# sensor-header.net
KiCad netlist of a schematic drawn in Altium Designer
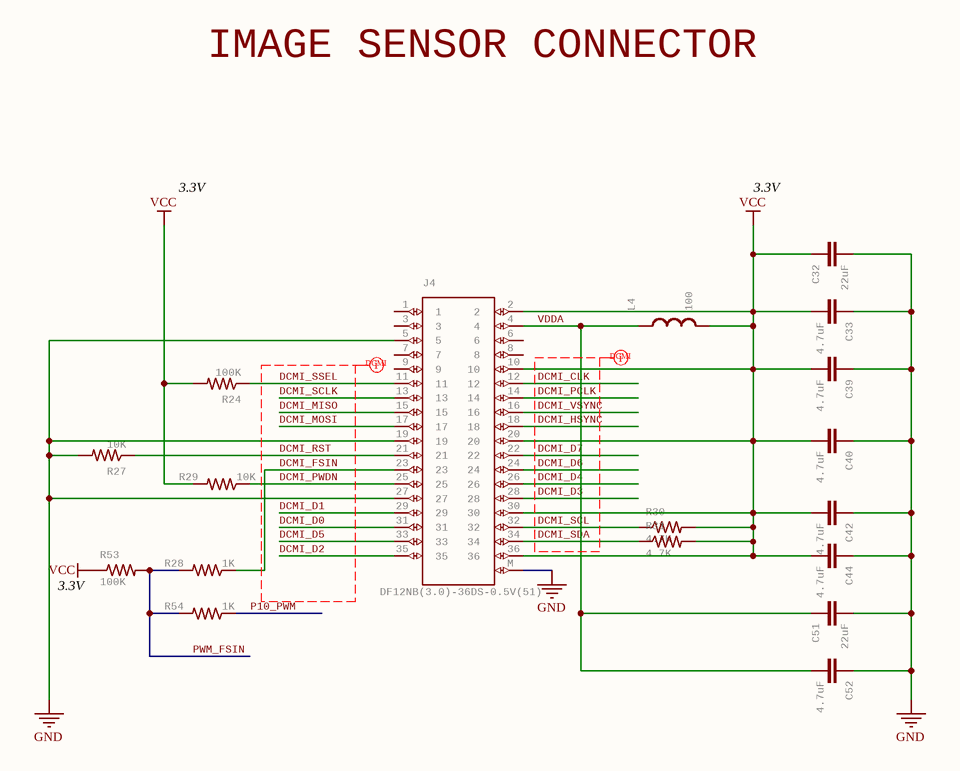
[diagram p0: sensor-header.SchDoc]

(export (version "E")
  (design (tool "Eeschema 10.0.6"))
  (components
    (comp (ref "C32")
      (value "22uF")
      (footprint "0805")
      (fields (field (name "MPN") "CL21A226MQQNNNE"))
      (libsource (lib "rt10") (part "22UF-0805-6.3V-20%"))
    )
    (comp (ref "C33")
      (value "4.7uF")
      (footprint "0402-CAP")
      (description "CapacitorStandard 0603 ceramic capacitor, and 0.1\" leaded capacitor.")
      (fields (field (name "MPN") "JMK105BBJ475MV-F"))
      (libsource (lib "rt10") (part "CAP0402-CAP"))
    )
    (comp (ref "C39")
      (value "4.7uF")
      (footprint "0402-CAP")
      (description "CapacitorStandard 0603 ceramic capacitor, and 0.1\" leaded capacitor.")
      (fields (field (name "MPN") "JMK105BBJ475MV-F"))
      (libsource (lib "rt10") (part "CAP0402-CAP"))
    )
    (comp (ref "C40")
      (value "4.7uF")
      (footprint "0402-CAP")
      (description "CapacitorStandard 0603 ceramic capacitor, and 0.1\" leaded capacitor.")
      (fields (field (name "MPN") "JMK105BBJ475MV-F"))
      (libsource (lib "rt10") (part "CAP0402-CAP"))
    )
    (comp (ref "C42")
      (value "4.7uF")
      (footprint "0402-CAP")
      (description "CapacitorStandard 0603 ceramic capacitor, and 0.1\" leaded capacitor.")
      (fields (field (name "MPN") "JMK105BBJ475MV-F"))
      (libsource (lib "rt10") (part "CAP0402-CAP"))
    )
    (comp (ref "C44")
      (value "4.7uF")
      (footprint "0402-CAP")
      (description "CapacitorStandard 0603 ceramic capacitor, and 0.1\" leaded capacitor.")
      (fields (field (name "MPN") "JMK105BBJ475MV-F"))
      (libsource (lib "rt10") (part "CAP0402-CAP"))
    )
    (comp (ref "C51")
      (value "22uF")
      (footprint "0805")
      (fields (field (name "MPN") "CL21A226MQQNNNE"))
      (libsource (lib "rt10") (part "22UF-0805-6.3V-20%"))
    )
    (comp (ref "C52")
      (value "4.7uF")
      (footprint "0402-CAP")
      (description "CapacitorStandard 0603 ceramic capacitor, and 0.1\" leaded capacitor.")
      (fields (field (name "MPN") "JMK105BBJ475MV-F"))
      (libsource (lib "rt10") (part "CAP0402-CAP"))
    )
    (comp (ref "J4")
      (value "DF12NB(3.0)-36DS-0.5V(51)")
      (footprint "DF12-36-DS")
      (description "Header")
      (libsource (lib "rt10") (part "DF12-36-DS"))
    )
    (comp (ref "L4")
      (value "100")
      (footprint "C0402")
      (fields (field (name "MPN") "MFBM1V1005-101-R"))
      (libsource (lib "rt10") (part "INDUCTOR0402"))
    )
    (comp (ref "R24")
      (value "100K")
      (footprint "0402-RES")
      (description "ResistorBasic schematic elements and footprints for 0603, 1206, and PTH resistors.")
      (fields (field (name "MPN") "AC0402FR-07100KL"))
      (libsource (lib "rt10") (part "RESISTOR0402-RES"))
    )
    (comp (ref "R27")
      (value "10K")
      (footprint "0402-RES")
      (description "ResistorBasic schematic elements and footprints for 0603, 1206, and PTH resistors.")
      (fields (field (name "MPN") "AC0402FR-1310K"))
      (libsource (lib "rt10") (part "RESISTOR0402-RES"))
    )
    (comp (ref "R28")
      (value "1K")
      (footprint "0402-RES")
      (description "ResistorBasic schematic elements and footprints for 0603, 1206, and PTH resistors.")
      (fields (field (name "MPN") "CRCW04021K00FKEDC"))
      (libsource (lib "rt10") (part "RESISTOR0402-RES"))
    )
    (comp (ref "R29")
      (value "10K")
      (footprint "0402-RES")
      (description "ResistorBasic schematic elements and footprints for 0603, 1206, and PTH resistors.")
      (fields (field (name "MPN") "AC0402FR-1310K"))
      (libsource (lib "rt10") (part "RESISTOR0402-RES"))
    )
    (comp (ref "R30")
      (value "4.7K")
      (footprint "0402-RES")
      (description "ResistorBasic schematic elements and footprints for 0603, 1206, and PTH resistors.")
      (fields (field (name "MPN") "AC0402FR-074K7L"))
      (libsource (lib "rt10") (part "RESISTOR0402-RES"))
    )
    (comp (ref "R31")
      (value "4.7K")
      (footprint "0402-RES")
      (description "ResistorBasic schematic elements and footprints for 0603, 1206, and PTH resistors.")
      (fields (field (name "MPN") "AC0402FR-074K7L"))
      (libsource (lib "rt10") (part "RESISTOR0402-RES"))
    )
    (comp (ref "R53")
      (value "100K")
      (footprint "0402-RES")
      (description "ResistorBasic schematic elements and footprints for 0603, 1206, and PTH resistors.")
      (fields (field (name "MPN") "AC0402FR-07100KL"))
      (libsource (lib "rt10") (part "RESISTOR0402-RES"))
    )
    (comp (ref "R54")
      (value "1K")
      (footprint "0402-RES")
      (description "ResistorBasic schematic elements and footprints for 0603, 1206, and PTH resistors.")
      (fields (field (name "MPN") "CRCW04021K00FKEDC"))
      (libsource (lib "rt10") (part "RESISTOR0402-RES"))
    )
  )
  (nets
    (net (code "1") (name "/DCMI_CLK") (class "Default")
      (node (ref "J4") (pin "12") (pinfunction "12_12") (pintype "bidirectional"))
    )
    (net (code "2") (name "/DCMI_D0") (class "Default")
      (node (ref "J4") (pin "31") (pinfunction "31_31") (pintype "bidirectional"))
    )
    (net (code "3") (name "/DCMI_D1") (class "Default")
      (node (ref "J4") (pin "29") (pinfunction "29_29") (pintype "bidirectional"))
    )
    (net (code "4") (name "/DCMI_D2") (class "Default")
      (node (ref "J4") (pin "35") (pinfunction "35_35") (pintype "bidirectional"))
    )
    (net (code "5") (name "/DCMI_D3") (class "Default")
      (node (ref "J4") (pin "28") (pinfunction "28_28") (pintype "bidirectional"))
    )
    (net (code "6") (name "/DCMI_D4") (class "Default")
      (node (ref "J4") (pin "26") (pinfunction "26_26") (pintype "bidirectional"))
    )
    (net (code "7") (name "/DCMI_D5") (class "Default")
      (node (ref "J4") (pin "33") (pinfunction "33_33") (pintype "bidirectional"))
    )
    (net (code "8") (name "/DCMI_D6") (class "Default")
      (node (ref "J4") (pin "24") (pinfunction "24_24") (pintype "bidirectional"))
    )
    (net (code "9") (name "/DCMI_D7") (class "Default")
      (node (ref "J4") (pin "22") (pinfunction "22_22") (pintype "bidirectional"))
    )
    (net (code "10") (name "/DCMI_FSIN") (class "Default")
      (node (ref "J4") (pin "23") (pinfunction "23_23") (pintype "bidirectional"))
      (node (ref "R28") (pin "1") (pinfunction "1_1") (pintype "passive"))
    )
    (net (code "11") (name "/DCMI_HSYNC") (class "Default")
      (node (ref "J4") (pin "18") (pinfunction "18_18") (pintype "bidirectional"))
    )
    (net (code "12") (name "/DCMI_MISO") (class "Default")
      (node (ref "J4") (pin "15") (pinfunction "15_15") (pintype "bidirectional"))
    )
    (net (code "13") (name "/DCMI_MOSI") (class "Default")
      (node (ref "J4") (pin "17") (pinfunction "17_17") (pintype "bidirectional"))
    )
    (net (code "14") (name "/DCMI_PCLK") (class "Default")
      (node (ref "J4") (pin "14") (pinfunction "14_14") (pintype "bidirectional"))
    )
    (net (code "15") (name "/DCMI_PWDN") (class "Default")
      (node (ref "J4") (pin "25") (pinfunction "25_25") (pintype "bidirectional"))
      (node (ref "R29") (pin "1") (pinfunction "1_1") (pintype "passive"))
    )
    (net (code "16") (name "/DCMI_RST") (class "Default")
      (node (ref "J4") (pin "21") (pinfunction "21_21") (pintype "bidirectional"))
      (node (ref "R27") (pin "1") (pinfunction "1_1") (pintype "passive"))
    )
    (net (code "17") (name "/DCMI_SCL") (class "Default")
      (node (ref "J4") (pin "32") (pinfunction "32_32") (pintype "bidirectional"))
      (node (ref "R30") (pin "1") (pinfunction "1_1") (pintype "passive"))
    )
    (net (code "18") (name "/DCMI_SCLK") (class "Default")
      (node (ref "J4") (pin "13") (pinfunction "13_13") (pintype "bidirectional"))
    )
    (net (code "19") (name "/DCMI_SDA") (class "Default")
      (node (ref "J4") (pin "34") (pinfunction "34_34") (pintype "bidirectional"))
      (node (ref "R31") (pin "1") (pinfunction "1_1") (pintype "passive"))
    )
    (net (code "20") (name "/DCMI_SSEL") (class "Default")
      (node (ref "J4") (pin "11") (pinfunction "11_11") (pintype "bidirectional"))
      (node (ref "R24") (pin "1") (pinfunction "1_1") (pintype "passive"))
    )
    (net (code "21") (name "/DCMI_VSYNC") (class "Default")
      (node (ref "J4") (pin "16") (pinfunction "16_16") (pintype "bidirectional"))
    )
    (net (code "22") (name "/P10_PWM") (class "Default")
      (node (ref "R54") (pin "1") (pinfunction "1_1") (pintype "passive"))
    )
    (net (code "23") (name "/PWM_FSIN") (class "Default")
      (node (ref "R28") (pin "2") (pinfunction "2_2") (pintype "passive"))
      (node (ref "R53") (pin "2") (pinfunction "2_2") (pintype "passive"))
      (node (ref "R54") (pin "2") (pinfunction "2_2") (pintype "passive"))
    )
    (net (code "24") (name "/VDDA") (class "Default")
      (node (ref "C51") (pin "1") (pinfunction "1_1") (pintype "passive"))
      (node (ref "C52") (pin "2") (pinfunction "2_2") (pintype "passive"))
      (node (ref "J4") (pin "4") (pinfunction "4_4") (pintype "bidirectional"))
      (node (ref "L4") (pin "1") (pinfunction "1_1") (pintype "passive"))
    )
    (net (code "25") (name "GND") (class "Default")
      (node (ref "C32") (pin "2") (pinfunction "2_2") (pintype "passive"))
      (node (ref "C33") (pin "1") (pinfunction "1_1") (pintype "passive"))
      (node (ref "C39") (pin "1") (pinfunction "1_1") (pintype "passive"))
      (node (ref "C40") (pin "1") (pinfunction "1_1") (pintype "passive"))
      (node (ref "C42") (pin "1") (pinfunction "1_1") (pintype "passive"))
      (node (ref "C44") (pin "1") (pinfunction "1_1") (pintype "passive"))
      (node (ref "C51") (pin "2") (pinfunction "2_2") (pintype "passive"))
      (node (ref "C52") (pin "1") (pinfunction "1_1") (pintype "passive"))
      (node (ref "J4") (pin "19") (pinfunction "19_19") (pintype "bidirectional"))
      (node (ref "J4") (pin "27") (pinfunction "27_27") (pintype "bidirectional"))
      (node (ref "J4") (pin "5") (pinfunction "5_5") (pintype "bidirectional"))
      (node (ref "J4") (pin "M") (pinfunction "M_M") (pintype "bidirectional"))
      (node (ref "R27") (pin "2") (pinfunction "2_2") (pintype "passive"))
    )
    (net (code "26") (name "VCC") (class "Default")
      (node (ref "C32") (pin "1") (pinfunction "1_1") (pintype "passive"))
      (node (ref "C33") (pin "2") (pinfunction "2_2") (pintype "passive"))
      (node (ref "C39") (pin "2") (pinfunction "2_2") (pintype "passive"))
      (node (ref "C40") (pin "2") (pinfunction "2_2") (pintype "passive"))
      (node (ref "C42") (pin "2") (pinfunction "2_2") (pintype "passive"))
      (node (ref "C44") (pin "2") (pinfunction "2_2") (pintype "passive"))
      (node (ref "J4") (pin "10") (pinfunction "10_10") (pintype "bidirectional"))
      (node (ref "J4") (pin "2") (pinfunction "2_2") (pintype "bidirectional"))
      (node (ref "J4") (pin "20") (pinfunction "20_20") (pintype "bidirectional"))
      (node (ref "J4") (pin "30") (pinfunction "30_30") (pintype "bidirectional"))
      (node (ref "J4") (pin "36") (pinfunction "36_36") (pintype "bidirectional"))
      (node (ref "L4") (pin "2") (pinfunction "2_2") (pintype "passive"))
      (node (ref "R24") (pin "2") (pinfunction "2_2") (pintype "passive"))
      (node (ref "R29") (pin "2") (pinfunction "2_2") (pintype "passive"))
      (node (ref "R30") (pin "2") (pinfunction "2_2") (pintype "passive"))
      (node (ref "R31") (pin "2") (pinfunction "2_2") (pintype "passive"))
      (node (ref "R53") (pin "1") (pinfunction "1_1") (pintype "passive"))
    )
    (net (code "27") (name "unconnected-(J4-Pad1)") (class "Default")
      (node (ref "J4") (pin "1") (pinfunction "1_1") (pintype "bidirectional"))
    )
    (net (code "28") (name "unconnected-(J4-Pad3)") (class "Default")
      (node (ref "J4") (pin "3") (pinfunction "3_3") (pintype "bidirectional"))
    )
    (net (code "29") (name "unconnected-(J4-Pad6)") (class "Default")
      (node (ref "J4") (pin "6") (pinfunction "6_6") (pintype "bidirectional"))
    )
    (net (code "30") (name "unconnected-(J4-Pad7)") (class "Default")
      (node (ref "J4") (pin "7") (pinfunction "7_7") (pintype "bidirectional"))
    )
    (net (code "31") (name "unconnected-(J4-Pad8)") (class "Default")
      (node (ref "J4") (pin "8") (pinfunction "8_8") (pintype "bidirectional"))
    )
    (net (code "32") (name "unconnected-(J4-Pad9)") (class "Default")
      (node (ref "J4") (pin "9") (pinfunction "9_9") (pintype "bidirectional"))
    )
  )
)
